# SAMD11_Feather_20SOIC.net
KiCad netlist of a schematic drawn in EAGLE
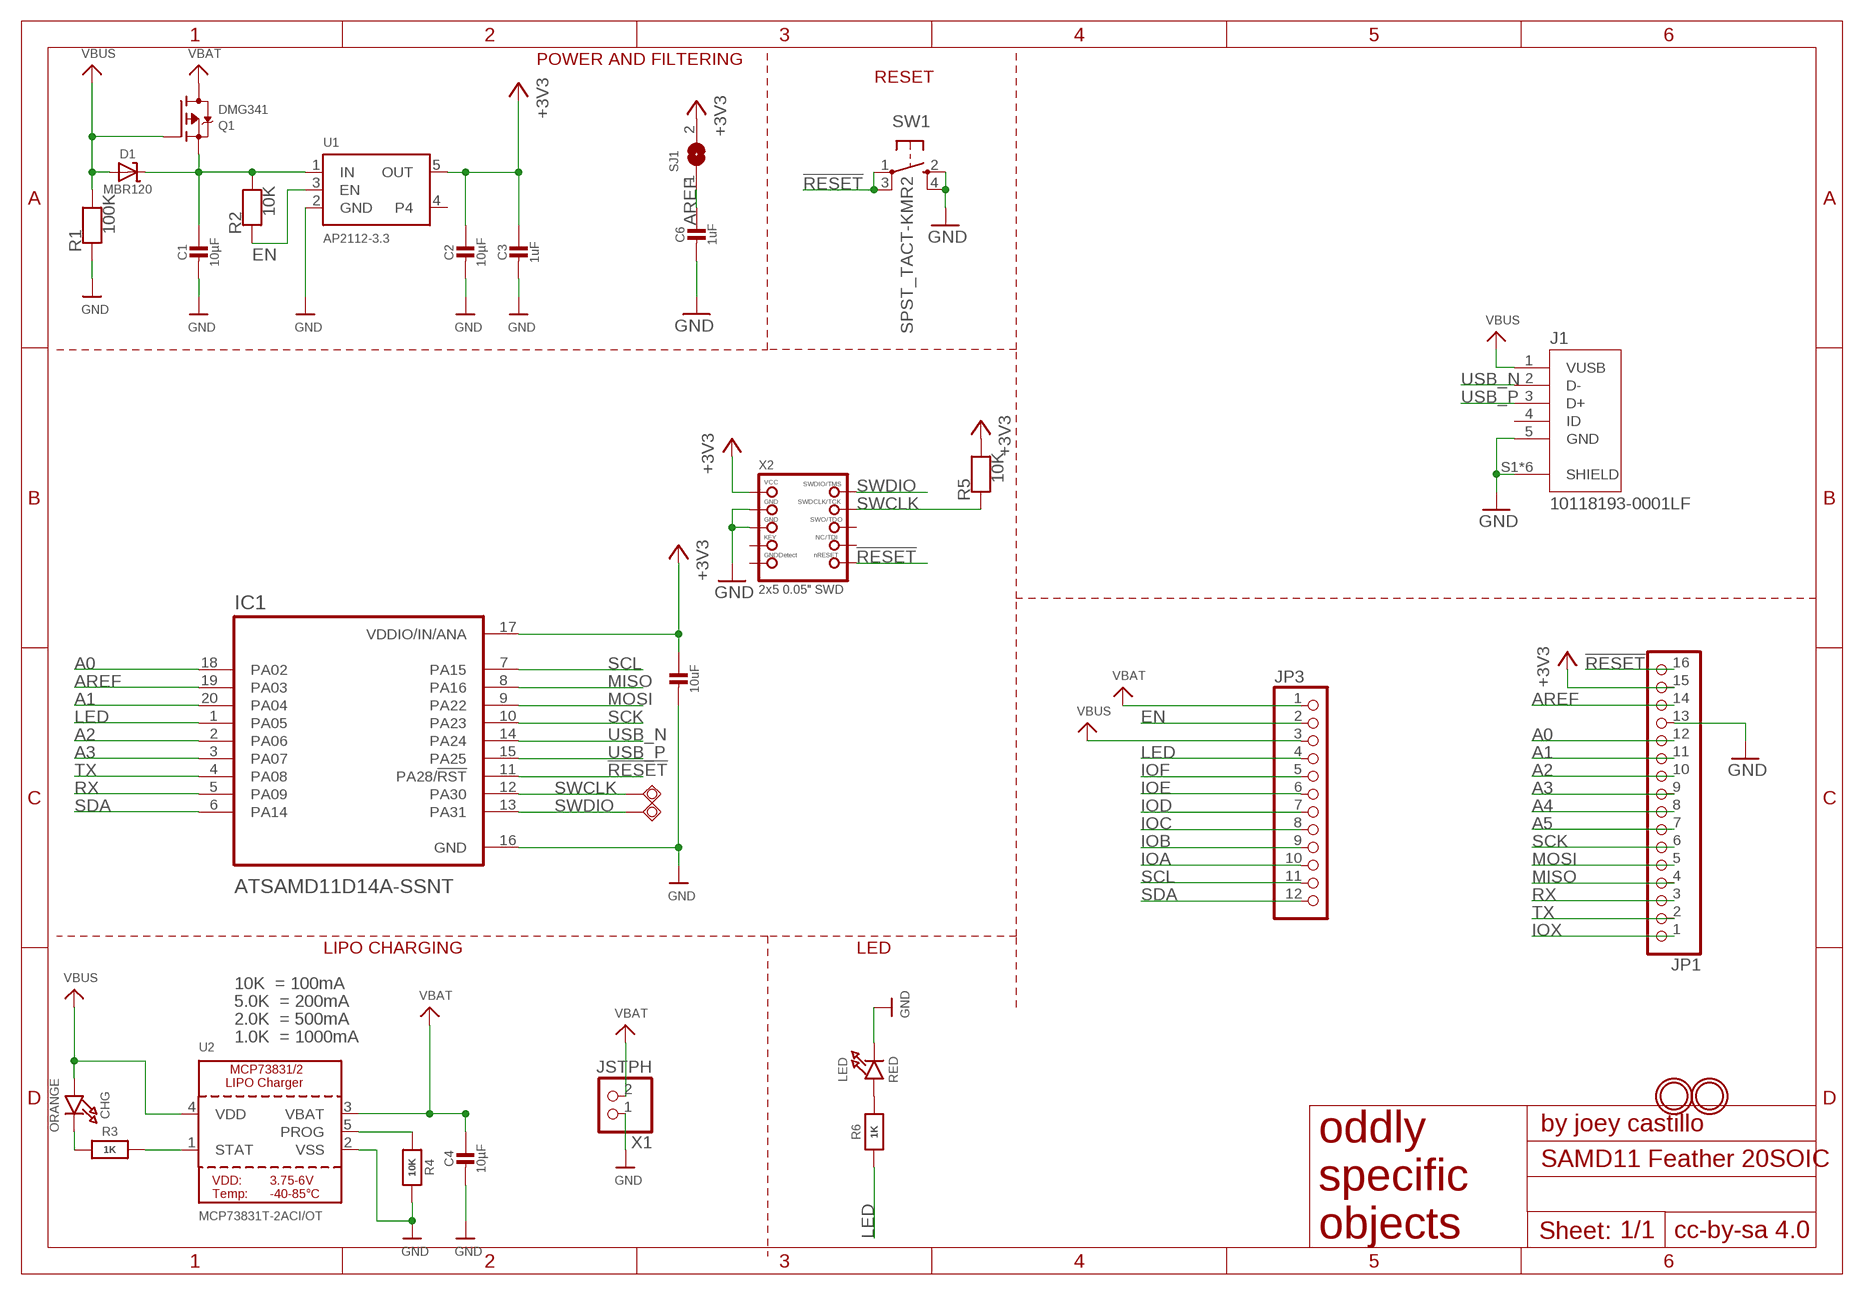
[diagram p0: schematic, sheet 1]

(export (version "E")
  (design (tool "Eeschema 10.0.6"))
  (components
    (comp (ref "C1")
      (value "10µF")
      (footprint "eagle-import:0805-NO")
      (libsource (lib "eagle-import") (part "CAP_CERAMIC0805-NOOUTLINE"))
    )
    (comp (ref "C2")
      (value "10µF")
      (footprint "eagle-import:0805-NO")
      (libsource (lib "eagle-import") (part "CAP_CERAMIC0805-NOOUTLINE"))
    )
    (comp (ref "C3")
      (value "1uF")
      (footprint "eagle-import:0805-NO")
      (libsource (lib "eagle-import") (part "CAP_CERAMIC0805-NOOUTLINE"))
    )
    (comp (ref "C4")
      (value "10µF")
      (footprint "eagle-import:0805-NO")
      (libsource (lib "eagle-import") (part "CAP_CERAMIC0805-NOOUTLINE"))
    )
    (comp (ref "C5")
      (value "10uF")
      (footprint "eagle-import:0805-NO")
      (libsource (lib "eagle-import") (part "CAP_CERAMIC0805-NOOUTLINE"))
    )
    (comp (ref "C6")
      (value "1uF")
      (footprint "eagle-import:0805-NO")
      (libsource (lib "eagle-import") (part "CAP_CERAMIC0805-NOOUTLINE"))
    )
    (comp (ref "CHG")
      (value "ORANGE")
      (footprint "eagle-import:CHIPLED_0805_NOOUTLINE")
      (libsource (lib "eagle-import") (part "LED0805_NOOUTLINE"))
    )
    (comp (ref "D1")
      (value "MBR120")
      (footprint "eagle-import:SOD-123")
      (libsource (lib "eagle-import") (part "DIODE-SCHOTTKYSOD-123"))
    )
    (comp (ref "IC1")
      (value "ATSAMD11D14A-SSNT")
      (footprint "eagle-import:SOIC127P1030X265-20N")
      (fields (field (name "MF") "Microchip"))
      (libsource (lib "eagle-import") (part "ATSAMD11D14A-SSNT"))
    )
    (comp (ref "J1")
      (value "10118193-0001LF")
      (footprint "eagle-import:FCI_10118193-0001LF")
      (fields (field (name "DIGI-KEY_PART_NUMBER") "609-4616-1-ND") (field (name "MF") "Amphenol ICC"))
      (libsource (lib "eagle-import") (part "10118193-0001LF"))
    )
    (comp (ref "JP1")
      (value "HEADER-1X16_MIN")
      (footprint "eagle-import:1X16_ROUND_MIN")
      (libsource (lib "eagle-import") (part "HEADER-1X16_MIN"))
    )
    (comp (ref "JP3")
      (value "HEADER-1X12_MIN")
      (footprint "eagle-import:1X12_ROUND_MIN")
      (libsource (lib "eagle-import") (part "HEADER-1X12_MIN"))
    )
    (comp (ref "LED")
      (value "RED")
      (footprint "eagle-import:CHIPLED_0805_NOOUTLINE")
      (libsource (lib "eagle-import") (part "LED0805_NOOUTLINE"))
    )
    (comp (ref "Q1")
      (value "DMG341")
      (footprint "eagle-import:SOT23-R")
      (libsource (lib "eagle-import") (part "MOSFET-P"))
    )
    (comp (ref "R1")
      (value "100K")
      (footprint "eagle-import:0805-NO")
      (libsource (lib "eagle-import") (part "RESISTOR0805_NOOUTLINE"))
    )
    (comp (ref "R2")
      (value "10K")
      (footprint "eagle-import:0805-NO")
      (libsource (lib "eagle-import") (part "RESISTOR0805_NOOUTLINE"))
    )
    (comp (ref "R3")
      (value "1K")
      (footprint "eagle-import:0805-NO")
      (libsource (lib "eagle-import") (part "RESISTOR0805_NOOUTLINE"))
    )
    (comp (ref "R4")
      (value "10K")
      (footprint "eagle-import:0805-NO")
      (libsource (lib "eagle-import") (part "RESISTOR0805_NOOUTLINE"))
    )
    (comp (ref "R5")
      (value "10K")
      (footprint "eagle-import:0805-NO")
      (libsource (lib "eagle-import") (part "RESISTOR0805_NOOUTLINE"))
    )
    (comp (ref "R6")
      (value "1K")
      (footprint "eagle-import:0805-NO")
      (libsource (lib "eagle-import") (part "RESISTOR0805_NOOUTLINE"))
    )
    (comp (ref "SJ1")
      (value "SOLDERJUMPERCLOSED")
      (footprint "eagle-import:SOLDERJUMPER_CLOSEDWIRE")
      (libsource (lib "eagle-import") (part "SOLDERJUMPERCLOSED"))
    )
    (comp (ref "SW1")
      (value "SPST_TACT-KMR2")
      (footprint "eagle-import:KMR2")
      (libsource (lib "eagle-import") (part "SPST_TACT-KMR2"))
    )
    (comp (ref "SWCLK")
      (value "TPSQTP20R")
      (footprint "eagle-import:TP20R")
      (libsource (lib "eagle-import") (part "TPSQTP20R"))
    )
    (comp (ref "SWDIO")
      (value "TPSQTP20R")
      (footprint "eagle-import:TP20R")
      (libsource (lib "eagle-import") (part "TPSQTP20R"))
    )
    (comp (ref "U$31")
      (value "MOUNTINGHOLE2.5")
      (footprint "eagle-import:MOUNTINGHOLE_2.5_PLATED")
      (libsource (lib "eagle-import") (part "MOUNTINGHOLE2.5"))
    )
    (comp (ref "U$32")
      (value "MOUNTINGHOLE2.5")
      (footprint "eagle-import:MOUNTINGHOLE_2.5_PLATED")
      (libsource (lib "eagle-import") (part "MOUNTINGHOLE2.5"))
    )
    (comp (ref "U1")
      (value "AP2112-3.3")
      (footprint "eagle-import:SOT23-5")
      (libsource (lib "eagle-import") (part "VREG_SOT23-5"))
    )
    (comp (ref "U2")
      (value "MCP73831T-2ACI/OT")
      (footprint "eagle-import:SOT23-5")
      (libsource (lib "eagle-import") (part "MCP73831/2"))
    )
    (comp (ref "X1")
      (value "JSTPH")
      (footprint "eagle-import:JSTPH2")
      (libsource (lib "eagle-import") (part "CON_JST_PH_2PIN"))
    )
    (comp (ref "X2")
      (value "2x5 0.05\" SWD")
      (footprint "eagle-import:2X05_1.27MM_BOX_POSTS")
      (libsource (lib "eagle-import") (part "JTAG-CORTEXBOXPOSTS"))
    )
  )
  (nets
    (net (code "1") (name "+3V3") (class "Default")
      (node (ref "C2") (pin "1") (pinfunction "1_1") (pintype "passive"))
      (node (ref "C3") (pin "1") (pinfunction "1_1") (pintype "passive"))
      (node (ref "C5") (pin "1") (pinfunction "1_1") (pintype "passive"))
      (node (ref "IC1") (pin "17") (pinfunction "VDDIO/IN/ANA_17") (pintype "power_in"))
      (node (ref "JP1") (pin "15") (pinfunction "15_15") (pintype "passive"))
      (node (ref "R5") (pin "2") (pinfunction "2_2") (pintype "passive"))
      (node (ref "SJ1") (pin "2") (pinfunction "2_2") (pintype "passive"))
      (node (ref "U1") (pin "5") (pinfunction "OUT_5") (pintype "power_in"))
      (node (ref "X2") (pin "1") (pinfunction "VCC_1") (pintype "power_in"))
    )
    (net (code "2") (name "/A0") (class "Default")
      (node (ref "IC1") (pin "18") (pinfunction "PA02_18") (pintype "bidirectional"))
      (node (ref "JP1") (pin "12") (pinfunction "12_12") (pintype "passive"))
    )
    (net (code "3") (name "/A1") (class "Default")
      (node (ref "IC1") (pin "20") (pinfunction "PA04_20") (pintype "bidirectional"))
      (node (ref "JP1") (pin "11") (pinfunction "11_11") (pintype "passive"))
    )
    (net (code "4") (name "/A2") (class "Default")
      (node (ref "IC1") (pin "2") (pinfunction "PA06_2") (pintype "bidirectional"))
      (node (ref "JP1") (pin "10") (pinfunction "10_10") (pintype "passive"))
    )
    (net (code "5") (name "/A3") (class "Default")
      (node (ref "IC1") (pin "3") (pinfunction "PA07_3") (pintype "bidirectional"))
      (node (ref "JP1") (pin "9") (pinfunction "9_9") (pintype "passive"))
    )
    (net (code "6") (name "/A4") (class "Default")
      (node (ref "JP1") (pin "8") (pinfunction "8_8") (pintype "passive"))
    )
    (net (code "7") (name "/A5") (class "Default")
      (node (ref "JP1") (pin "7") (pinfunction "7_7") (pintype "passive"))
    )
    (net (code "8") (name "/AREF") (class "Default")
      (node (ref "C6") (pin "1") (pinfunction "1_1") (pintype "passive"))
      (node (ref "IC1") (pin "19") (pinfunction "PA03_19") (pintype "bidirectional"))
      (node (ref "JP1") (pin "14") (pinfunction "14_14") (pintype "passive"))
      (node (ref "SJ1") (pin "1") (pinfunction "1_1") (pintype "passive"))
    )
    (net (code "9") (name "/EN") (class "Default")
      (node (ref "JP3") (pin "2") (pinfunction "2_2") (pintype "passive"))
      (node (ref "R2") (pin "1") (pinfunction "1_1") (pintype "passive"))
      (node (ref "U1") (pin "3") (pinfunction "EN_3") (pintype "input"))
    )
    (net (code "10") (name "/IOA") (class "Default")
      (node (ref "JP3") (pin "10") (pinfunction "10_10") (pintype "passive"))
    )
    (net (code "11") (name "/IOB") (class "Default")
      (node (ref "JP3") (pin "9") (pinfunction "9_9") (pintype "passive"))
    )
    (net (code "12") (name "/IOC") (class "Default")
      (node (ref "JP3") (pin "8") (pinfunction "8_8") (pintype "passive"))
    )
    (net (code "13") (name "/IOD") (class "Default")
      (node (ref "JP3") (pin "7") (pinfunction "7_7") (pintype "passive"))
    )
    (net (code "14") (name "/IOE") (class "Default")
      (node (ref "JP3") (pin "6") (pinfunction "6_6") (pintype "passive"))
    )
    (net (code "15") (name "/IOF") (class "Default")
      (node (ref "JP3") (pin "5") (pinfunction "5_5") (pintype "passive"))
    )
    (net (code "16") (name "/IOX") (class "Default")
      (node (ref "JP1") (pin "1") (pinfunction "1_1") (pintype "passive"))
    )
    (net (code "17") (name "/LED") (class "Default")
      (node (ref "IC1") (pin "1") (pinfunction "PA05_1") (pintype "bidirectional"))
      (node (ref "JP3") (pin "4") (pinfunction "4_4") (pintype "passive"))
      (node (ref "R6") (pin "1") (pinfunction "1_1") (pintype "passive"))
    )
    (net (code "18") (name "/MISO") (class "Default")
      (node (ref "IC1") (pin "8") (pinfunction "PA16_8") (pintype "bidirectional"))
      (node (ref "JP1") (pin "4") (pinfunction "4_4") (pintype "passive"))
    )
    (net (code "19") (name "/MOSI") (class "Default")
      (node (ref "IC1") (pin "9") (pinfunction "PA22_9") (pintype "bidirectional"))
      (node (ref "JP1") (pin "5") (pinfunction "5_5") (pintype "passive"))
    )
    (net (code "20") (name "/RX") (class "Default")
      (node (ref "IC1") (pin "5") (pinfunction "PA09_5") (pintype "bidirectional"))
      (node (ref "JP1") (pin "3") (pinfunction "3_3") (pintype "passive"))
    )
    (net (code "21") (name "/SCK") (class "Default")
      (node (ref "IC1") (pin "10") (pinfunction "PA23_10") (pintype "bidirectional"))
      (node (ref "JP1") (pin "6") (pinfunction "6_6") (pintype "passive"))
    )
    (net (code "22") (name "/SCL") (class "Default")
      (node (ref "IC1") (pin "7") (pinfunction "PA15_7") (pintype "bidirectional"))
      (node (ref "JP3") (pin "11") (pinfunction "11_11") (pintype "passive"))
    )
    (net (code "23") (name "/SDA") (class "Default")
      (node (ref "IC1") (pin "6") (pinfunction "PA14_6") (pintype "bidirectional"))
      (node (ref "JP3") (pin "12") (pinfunction "12_12") (pintype "passive"))
    )
    (net (code "24") (name "/SWCLK") (class "Default")
      (node (ref "IC1") (pin "12") (pinfunction "PA30_12") (pintype "bidirectional"))
      (node (ref "R5") (pin "1") (pinfunction "1_1") (pintype "passive"))
      (node (ref "SWCLK") (pin "TP") (pinfunction "TP_TP") (pintype "input"))
      (node (ref "X2") (pin "4") (pinfunction "SWDCLK_4") (pintype "bidirectional"))
    )
    (net (code "25") (name "/SWDIO") (class "Default")
      (node (ref "IC1") (pin "13") (pinfunction "PA31_13") (pintype "bidirectional"))
      (node (ref "SWDIO") (pin "TP") (pinfunction "TP_TP") (pintype "input"))
      (node (ref "X2") (pin "2") (pinfunction "SWDIO_2") (pintype "bidirectional"))
    )
    (net (code "26") (name "/TX") (class "Default")
      (node (ref "IC1") (pin "4") (pinfunction "PA08_4") (pintype "bidirectional"))
      (node (ref "JP1") (pin "2") (pinfunction "2_2") (pintype "passive"))
    )
    (net (code "27") (name "/USB_N") (class "Default")
      (node (ref "IC1") (pin "14") (pinfunction "PA24_14") (pintype "bidirectional"))
      (node (ref "J1") (pin "2") (pinfunction "D-_2") (pintype "passive"))
    )
    (net (code "28") (name "/USB_P") (class "Default")
      (node (ref "IC1") (pin "15") (pinfunction "PA25_15") (pintype "bidirectional"))
      (node (ref "J1") (pin "3") (pinfunction "D+_3") (pintype "passive"))
    )
    (net (code "29") (name "/~{RESET}") (class "Default")
      (node (ref "IC1") (pin "11") (pinfunction "PA28/~{RST}_11") (pintype "bidirectional"))
      (node (ref "JP1") (pin "16") (pinfunction "16_16") (pintype "passive"))
      (node (ref "SW1") (pin "1") (pinfunction "P_1") (pintype "passive"))
      (node (ref "SW1") (pin "3") (pinfunction "P1_3") (pintype "passive"))
      (node (ref "X2") (pin "10") (pinfunction "NRESET_10") (pintype "bidirectional"))
    )
    (net (code "30") (name "GND") (class "Default")
      (node (ref "C1") (pin "2") (pinfunction "2_2") (pintype "passive"))
      (node (ref "C2") (pin "2") (pinfunction "2_2") (pintype "passive"))
      (node (ref "C3") (pin "2") (pinfunction "2_2") (pintype "passive"))
      (node (ref "C4") (pin "2") (pinfunction "2_2") (pintype "passive"))
      (node (ref "C5") (pin "2") (pinfunction "2_2") (pintype "passive"))
      (node (ref "C6") (pin "2") (pinfunction "2_2") (pintype "passive"))
      (node (ref "IC1") (pin "16") (pinfunction "GND_16") (pintype "power_in"))
      (node (ref "J1") (pin "5") (pinfunction "GND_5") (pintype "passive"))
      (node (ref "J1") (pin "S1") (pinfunction "SHIELD_S1") (pintype "passive"))
      (node (ref "J1") (pin "S2") (pinfunction "SHIELD_S2") (pintype "passive"))
      (node (ref "J1") (pin "S3") (pinfunction "SHIELD_S3") (pintype "passive"))
      (node (ref "J1") (pin "S4") (pinfunction "SHIELD_S4") (pintype "passive"))
      (node (ref "J1") (pin "S5") (pinfunction "SHIELD_S5") (pintype "passive"))
      (node (ref "J1") (pin "S6") (pinfunction "SHIELD_S6") (pintype "passive"))
      (node (ref "JP1") (pin "13") (pinfunction "13_13") (pintype "passive"))
      (node (ref "LED") (pin "C") (pinfunction "C_C") (pintype "passive"))
      (node (ref "R1") (pin "1") (pinfunction "1_1") (pintype "passive"))
      (node (ref "R4") (pin "2") (pinfunction "2_2") (pintype "passive"))
      (node (ref "SW1") (pin "2") (pinfunction "S_2") (pintype "passive"))
      (node (ref "SW1") (pin "4") (pinfunction "S1_4") (pintype "passive"))
      (node (ref "U1") (pin "2") (pinfunction "GND_2") (pintype "power_in"))
      (node (ref "U2") (pin "2") (pinfunction "VSS_2") (pintype "power_in"))
      (node (ref "X1") (pin "1") (pinfunction "1_1") (pintype "passive"))
      (node (ref "X2") (pin "3") (pinfunction "GND_3") (pintype "power_in"))
      (node (ref "X2") (pin "5") (pinfunction "GND_5") (pintype "power_in"))
    )
    (net (code "31") (name "Net-(CHG-PadC)") (class "Default")
      (node (ref "CHG") (pin "C") (pinfunction "C_C") (pintype "passive"))
      (node (ref "R3") (pin "1") (pinfunction "1_1") (pintype "passive"))
    )
    (net (code "32") (name "Net-(LED-PadA)") (class "Default")
      (node (ref "LED") (pin "A") (pinfunction "A_A") (pintype "passive"))
      (node (ref "R6") (pin "2") (pinfunction "2_2") (pintype "passive"))
    )
    (net (code "33") (name "Net-(Q1-S)") (class "Default")
      (node (ref "C1") (pin "1") (pinfunction "1_1") (pintype "passive"))
      (node (ref "D1") (pin "C") (pinfunction "C_C") (pintype "passive"))
      (node (ref "Q1") (pin "2") (pinfunction "S_2") (pintype "passive"))
      (node (ref "R2") (pin "2") (pinfunction "2_2") (pintype "passive"))
      (node (ref "U1") (pin "1") (pinfunction "IN_1") (pintype "power_in"))
    )
    (net (code "34") (name "Net-(U2-PROG)") (class "Default")
      (node (ref "R4") (pin "1") (pinfunction "1_1") (pintype "passive"))
      (node (ref "U2") (pin "5") (pinfunction "PROG_5") (pintype "input"))
    )
    (net (code "35") (name "Net-(U2-STAT)") (class "Default")
      (node (ref "R3") (pin "2") (pinfunction "2_2") (pintype "passive"))
      (node (ref "U2") (pin "1") (pinfunction "STAT_1") (pintype "output"))
    )
    (net (code "36") (name "VBAT") (class "Default")
      (node (ref "C4") (pin "1") (pinfunction "1_1") (pintype "passive"))
      (node (ref "JP3") (pin "1") (pinfunction "1_1") (pintype "passive"))
      (node (ref "Q1") (pin "3") (pinfunction "D_3") (pintype "passive"))
      (node (ref "U2") (pin "3") (pinfunction "VBAT_3") (pintype "power_in"))
      (node (ref "X1") (pin "2") (pinfunction "2_2") (pintype "passive"))
    )
    (net (code "37") (name "VBUS") (class "Default")
      (node (ref "CHG") (pin "A") (pinfunction "A_A") (pintype "passive"))
      (node (ref "D1") (pin "A") (pinfunction "A_A") (pintype "passive"))
      (node (ref "J1") (pin "1") (pinfunction "VUSB_1") (pintype "passive"))
      (node (ref "JP3") (pin "3") (pinfunction "3_3") (pintype "passive"))
      (node (ref "Q1") (pin "1") (pinfunction "G_1") (pintype "passive"))
      (node (ref "R1") (pin "2") (pinfunction "2_2") (pintype "passive"))
      (node (ref "U2") (pin "4") (pinfunction "VDD_4") (pintype "power_in"))
    )
    (net (code "38") (name "unconnected-(J1-ID-Pad4)") (class "Default")
      (node (ref "J1") (pin "4") (pinfunction "ID_4") (pintype "passive"))
    )
    (net (code "39") (name "unconnected-(U1-P4-Pad4)") (class "Default")
      (node (ref "U1") (pin "4") (pinfunction "P4_4") (pintype "bidirectional"))
    )
    (net (code "40") (name "unconnected-(X2-GNDDETECT-Pad9)") (class "Default")
      (node (ref "X2") (pin "9") (pinfunction "GNDDETECT_9") (pintype "bidirectional"))
    )
    (net (code "41") (name "unconnected-(X2-KEY-Pad7)") (class "Default")
      (node (ref "X2") (pin "7") (pinfunction "KEY_7") (pintype "bidirectional"))
    )
    (net (code "42") (name "unconnected-(X2-SWO-Pad6)") (class "Default")
      (node (ref "X2") (pin "6") (pinfunction "SWO_6") (pintype "bidirectional"))
    )
    (net (code "43") (name "unconnected-(X2-TDI-Pad8)") (class "Default")
      (node (ref "X2") (pin "8") (pinfunction "TDI_8") (pintype "bidirectional"))
    )
  )
)
